# WB-test-V1.net
KiCad netlist of a schematic drawn in EAGLE
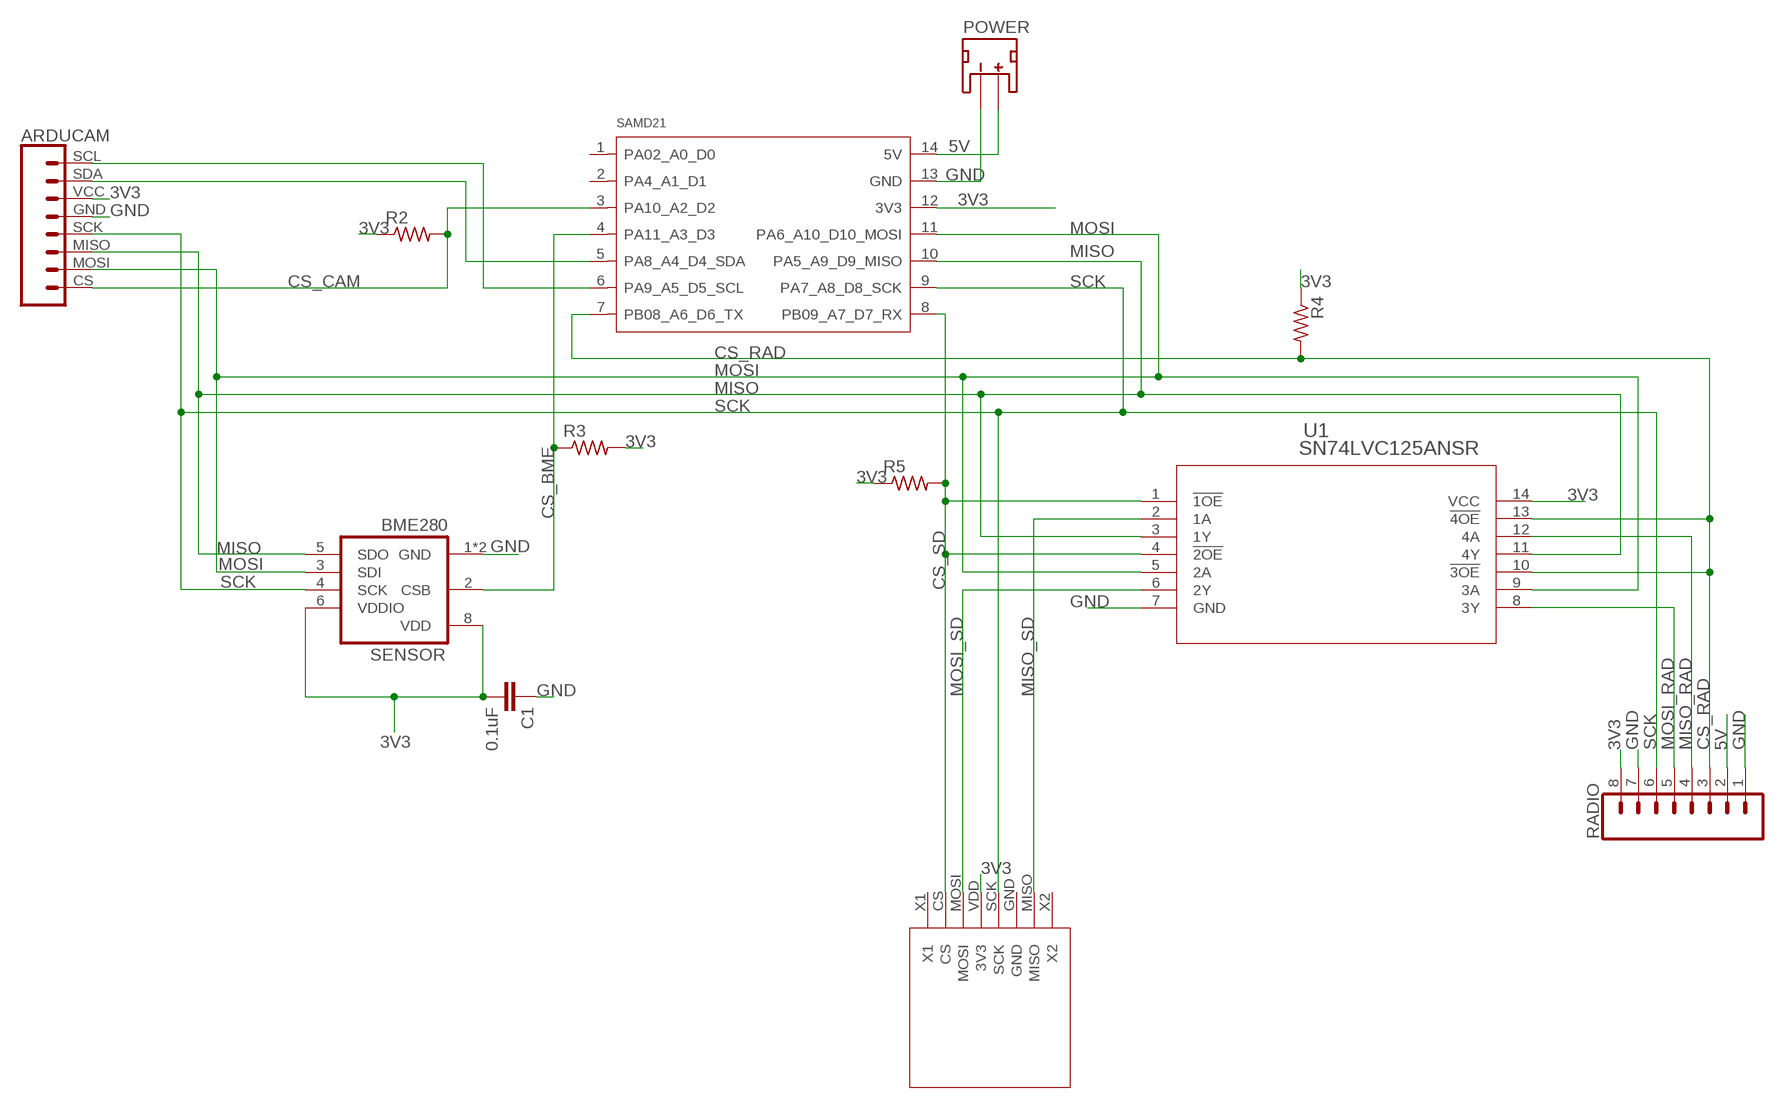
[diagram p0: schematic, sheet 1]

(export (version "E")
  (design (tool "Eeschema 10.0.6"))
  (components
    (comp (ref "C1")
      (value "0.1uF")
      (footprint "eagle-import:0402")
      (libsource (lib "eagle-import") (part "0.1UF-0402-16V-10%"))
    )
    (comp (ref "CAM")
      (value "ARDUCAM_MINI")
      (footprint "eagle-import:ARDUCAM_MINI")
      (libsource (lib "eagle-import") (part "ARDUCAM_MINI"))
    )
    (comp (ref "POWER")
      (value "JST_2MM_MALE")
      (footprint "eagle-import:JST-2-SMD")
      (libsource (lib "eagle-import") (part "JST_2MM_MALE"))
    )
    (comp (ref "R2")
      (value "R-US_R0402")
      (footprint "eagle-import:R0402")
      (libsource (lib "eagle-import") (part "R-US_R0402"))
    )
    (comp (ref "R3")
      (value "R-US_R0402")
      (footprint "eagle-import:R0402")
      (libsource (lib "eagle-import") (part "R-US_R0402"))
    )
    (comp (ref "R4")
      (value "R-US_R0402")
      (footprint "eagle-import:R0402")
      (libsource (lib "eagle-import") (part "R-US_R0402"))
    )
    (comp (ref "R5")
      (value "R-US_R0402")
      (footprint "eagle-import:R0402")
      (libsource (lib "eagle-import") (part "R-US_R0402"))
    )
    (comp (ref "RADIO")
      (value "CONN_08\"")
      (footprint "eagle-import:1X08")
      (libsource (lib "eagle-import") (part "CONN_08{dblquote}"))
    )
    (comp (ref "SAMD21")
      (value "MOUDLE-SEEEDUINO-XIAO")
      (footprint "eagle-import:MOUDLE14P-2.54-21X17.8MM")
      (libsource (lib "eagle-import") (part "MOUDLE-SEEEDUINO-XIAO"))
    )
    (comp (ref "SD")
      (value "SD_READER")
      (footprint "eagle-import:SDREAD")
      (libsource (lib "eagle-import") (part "SD_READER"))
    )
    (comp (ref "SENSOR")
      (value "BME280")
      (footprint "eagle-import:BME280")
      (libsource (lib "eagle-import") (part "BME280"))
    )
    (comp (ref "U1")
      (value "SN74LVC125ANSR")
      (footprint "eagle-import:NS14")
      (fields (field (name "COPYRIGHT") "Copyright (C) 2024 Ultra Librarian. All rights reserved."))
      (libsource (lib "eagle-import") (part "SN74LVC125ANSR"))
    )
  )
  (nets
    (net (code "1") (name "/3V3") (class "Default")
      (node (ref "C1") (pin "2") (pinfunction "2_2") (pintype "passive"))
      (node (ref "CAM") (pin "VCC") (pinfunction "VCC_VCC") (pintype "passive"))
      (node (ref "R2") (pin "1") (pinfunction "1_1") (pintype "passive"))
      (node (ref "R3") (pin "2") (pinfunction "2_2") (pintype "passive"))
      (node (ref "R4") (pin "1") (pinfunction "1_1") (pintype "passive"))
      (node (ref "R5") (pin "1") (pinfunction "1_1") (pintype "passive"))
      (node (ref "RADIO") (pin "8") (pinfunction "8_8") (pintype "passive"))
      (node (ref "SAMD21") (pin "12") (pinfunction "3V3_12") (pintype "bidirectional"))
      (node (ref "SD") (pin "VDD") (pinfunction "3V3_VDD") (pintype "bidirectional"))
      (node (ref "SENSOR") (pin "6") (pinfunction "VDDIO_6") (pintype "power_in"))
      (node (ref "SENSOR") (pin "8") (pinfunction "VDD_8") (pintype "power_in"))
      (node (ref "U1") (pin "14") (pinfunction "VCC_14") (pintype "power_in"))
    )
    (net (code "2") (name "/5V") (class "Default")
      (node (ref "POWER") (pin "2") (pinfunction "+_2") (pintype "bidirectional"))
      (node (ref "RADIO") (pin "2") (pinfunction "2_2") (pintype "passive"))
      (node (ref "SAMD21") (pin "14") (pinfunction "5V_14") (pintype "bidirectional"))
    )
    (net (code "3") (name "/CS_BME") (class "Default")
      (node (ref "R3") (pin "1") (pinfunction "1_1") (pintype "passive"))
      (node (ref "SAMD21") (pin "4") (pinfunction "PA11_A3_D3_4") (pintype "bidirectional"))
      (node (ref "SENSOR") (pin "2") (pinfunction "CSB_2") (pintype "input"))
    )
    (net (code "4") (name "/CS_CAM") (class "Default")
      (node (ref "CAM") (pin "CS") (pinfunction "CS_CS") (pintype "passive"))
      (node (ref "R2") (pin "2") (pinfunction "2_2") (pintype "passive"))
      (node (ref "SAMD21") (pin "3") (pinfunction "PA10_A2_D2_3") (pintype "bidirectional"))
    )
    (net (code "5") (name "/CS_RAD") (class "Default")
      (node (ref "R4") (pin "2") (pinfunction "2_2") (pintype "passive"))
      (node (ref "RADIO") (pin "3") (pinfunction "3_3") (pintype "passive"))
      (node (ref "SAMD21") (pin "7") (pinfunction "PB08_A6_D6_TX_7") (pintype "bidirectional"))
      (node (ref "U1") (pin "10") (pinfunction "~{3OE}_10") (pintype "input"))
      (node (ref "U1") (pin "13") (pinfunction "~{4OE}_13") (pintype "input"))
    )
    (net (code "6") (name "/CS_SD") (class "Default")
      (node (ref "R5") (pin "2") (pinfunction "2_2") (pintype "passive"))
      (node (ref "SAMD21") (pin "8") (pinfunction "PB09_A7_D7_RX_8") (pintype "bidirectional"))
      (node (ref "SD") (pin "CS") (pinfunction "CS_CS") (pintype "bidirectional"))
      (node (ref "U1") (pin "1") (pinfunction "~{1OE}_1") (pintype "input"))
      (node (ref "U1") (pin "4") (pinfunction "~{2OE}_4") (pintype "input"))
    )
    (net (code "7") (name "/GND") (class "Default")
      (node (ref "C1") (pin "1") (pinfunction "1_1") (pintype "passive"))
      (node (ref "CAM") (pin "GND") (pinfunction "GND_GND") (pintype "passive"))
      (node (ref "POWER") (pin "1") (pinfunction "-_1") (pintype "bidirectional"))
      (node (ref "RADIO") (pin "1") (pinfunction "1_1") (pintype "passive"))
      (node (ref "RADIO") (pin "7") (pinfunction "7_7") (pintype "passive"))
      (node (ref "SAMD21") (pin "13") (pinfunction "GND_13") (pintype "bidirectional"))
      (node (ref "SENSOR") (pin "1") (pinfunction "GND_1") (pintype "power_in"))
      (node (ref "SENSOR") (pin "7") (pinfunction "GND_7") (pintype "power_in"))
      (node (ref "U1") (pin "7") (pinfunction "GND_7") (pintype "power_in"))
    )
    (net (code "8") (name "/MISO") (class "Default")
      (node (ref "CAM") (pin "MISO") (pinfunction "MISO_MISO") (pintype "passive"))
      (node (ref "SAMD21") (pin "10") (pinfunction "PA5_A9_D9_MISO_10") (pintype "bidirectional"))
      (node (ref "SENSOR") (pin "5") (pinfunction "SDO_5") (pintype "input"))
      (node (ref "U1") (pin "11") (pinfunction "4Y_11") (pintype "output"))
      (node (ref "U1") (pin "3") (pinfunction "1Y_3") (pintype "output"))
    )
    (net (code "9") (name "/MISO_RAD") (class "Default")
      (node (ref "RADIO") (pin "4") (pinfunction "4_4") (pintype "passive"))
      (node (ref "U1") (pin "12") (pinfunction "4A_12") (pintype "input"))
    )
    (net (code "10") (name "/MISO_SD") (class "Default")
      (node (ref "SD") (pin "MISO") (pinfunction "MISO_MISO") (pintype "bidirectional"))
      (node (ref "U1") (pin "2") (pinfunction "1A_2") (pintype "input"))
    )
    (net (code "11") (name "/MOSI") (class "Default")
      (node (ref "CAM") (pin "MOSI") (pinfunction "MOSI_MOSI") (pintype "passive"))
      (node (ref "SAMD21") (pin "11") (pinfunction "PA6_A10_D10_MOSI_11") (pintype "bidirectional"))
      (node (ref "SENSOR") (pin "3") (pinfunction "SDI_3") (pintype "bidirectional"))
      (node (ref "U1") (pin "5") (pinfunction "2A_5") (pintype "input"))
      (node (ref "U1") (pin "9") (pinfunction "3A_9") (pintype "input"))
    )
    (net (code "12") (name "/MOSI_RAD") (class "Default")
      (node (ref "RADIO") (pin "5") (pinfunction "5_5") (pintype "passive"))
      (node (ref "U1") (pin "8") (pinfunction "3Y_8") (pintype "output"))
    )
    (net (code "13") (name "/MOSI_SD") (class "Default")
      (node (ref "SD") (pin "MOSI") (pinfunction "MOSI_MOSI") (pintype "bidirectional"))
      (node (ref "U1") (pin "6") (pinfunction "2Y_6") (pintype "output"))
    )
    (net (code "14") (name "/SCK") (class "Default")
      (node (ref "CAM") (pin "SCK") (pinfunction "SCK_SCK") (pintype "passive"))
      (node (ref "RADIO") (pin "6") (pinfunction "6_6") (pintype "passive"))
      (node (ref "SAMD21") (pin "9") (pinfunction "PA7_A8_D8_SCK_9") (pintype "bidirectional"))
      (node (ref "SD") (pin "SCK") (pinfunction "SCK_SCK") (pintype "bidirectional"))
      (node (ref "SENSOR") (pin "4") (pinfunction "SCK_4") (pintype "bidirectional"))
    )
    (net (code "15") (name "Net-(SAMD21-PA8_A4_D4_SDA)") (class "Default")
      (node (ref "CAM") (pin "SDA") (pinfunction "SDA_SDA") (pintype "passive"))
      (node (ref "SAMD21") (pin "5") (pinfunction "PA8_A4_D4_SDA_5") (pintype "bidirectional"))
    )
    (net (code "16") (name "Net-(SAMD21-PA9_A5_D5_SCL)") (class "Default")
      (node (ref "CAM") (pin "SCL") (pinfunction "SCL_SCL") (pintype "passive"))
      (node (ref "SAMD21") (pin "6") (pinfunction "PA9_A5_D5_SCL_6") (pintype "bidirectional"))
    )
    (net (code "17") (name "unconnected-(POWER-PAD1-PadNC1)") (class "Default")
      (node (ref "POWER") (pin "NC1") (pinfunction "PAD1_NC1") (pintype "bidirectional"))
    )
    (net (code "18") (name "unconnected-(POWER-PAD2-PadNC2)") (class "Default")
      (node (ref "POWER") (pin "NC2") (pinfunction "PAD2_NC2") (pintype "bidirectional"))
    )
    (net (code "19") (name "unconnected-(SAMD21-PA02_A0_D0-Pad1)") (class "Default")
      (node (ref "SAMD21") (pin "1") (pinfunction "PA02_A0_D0_1") (pintype "bidirectional"))
    )
    (net (code "20") (name "unconnected-(SAMD21-PA4_A1_D1-Pad2)") (class "Default")
      (node (ref "SAMD21") (pin "2") (pinfunction "PA4_A1_D1_2") (pintype "bidirectional"))
    )
    (net (code "21") (name "unconnected-(SD-PadGND)") (class "Default")
      (node (ref "SD") (pin "GND") (pinfunction "GND_GND") (pintype "bidirectional"))
    )
    (net (code "22") (name "unconnected-(SD-PadX1)") (class "Default")
      (node (ref "SD") (pin "X1") (pinfunction "X1_X1") (pintype "bidirectional"))
    )
    (net (code "23") (name "unconnected-(SD-PadX2)") (class "Default")
      (node (ref "SD") (pin "X2") (pinfunction "X2_X2") (pintype "bidirectional"))
    )
  )
)
